# ir_remote_v3.net
KiCad netlist of a schematic drawn in EAGLE
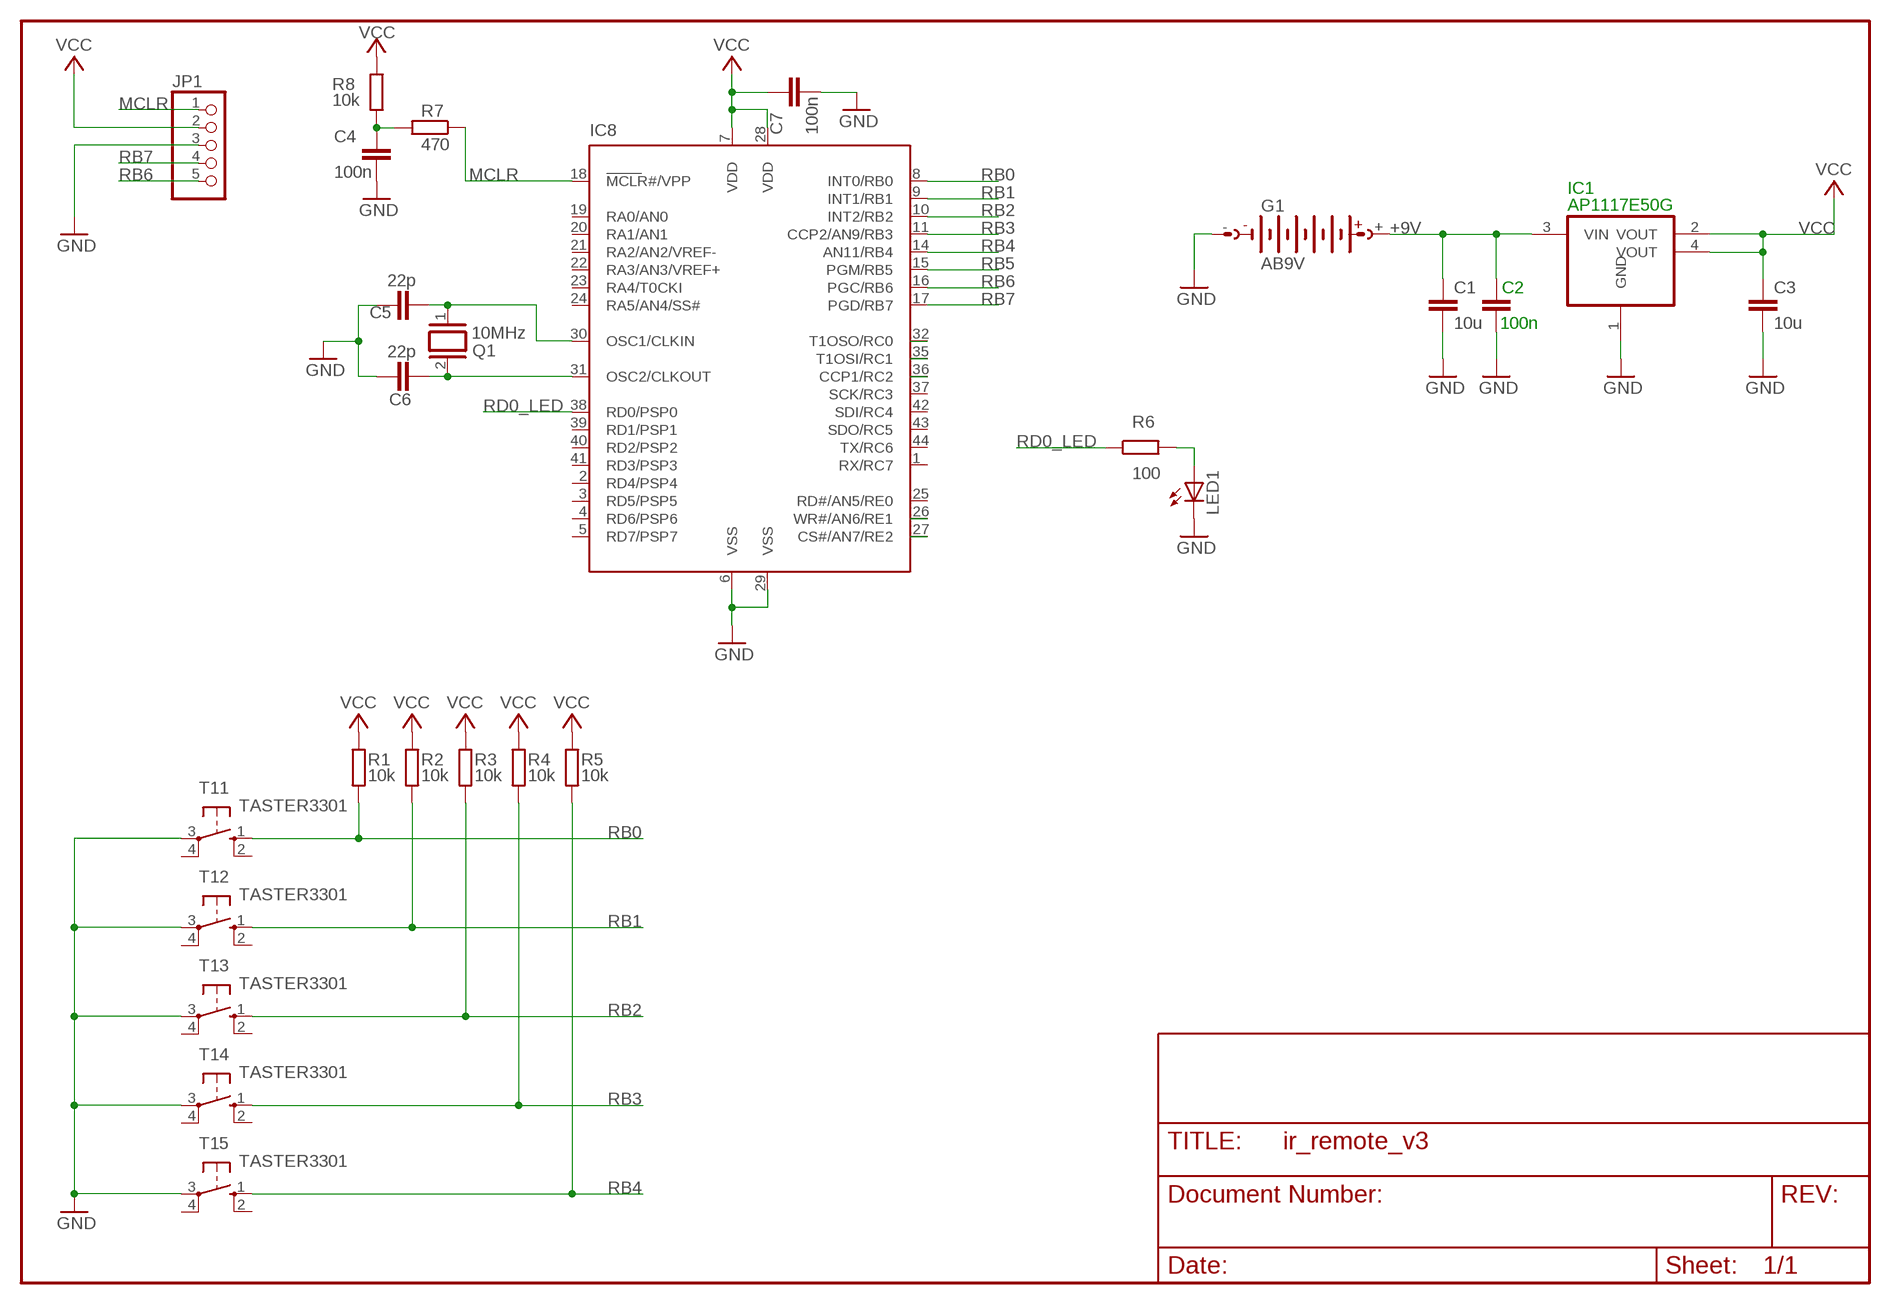
[diagram p0: schematic, sheet 1]

(export (version "E")
  (design (tool "Eeschema 10.0.6"))
  (components
    (comp (ref "C1")
      (value "10u")
      (footprint "eagle-import:C0805")
      (libsource (lib "eagle-import") (part "C-EUC0805"))
    )
    (comp (ref "C2")
      (value "100n")
      (footprint "eagle-import:C0805")
      (libsource (lib "eagle-import") (part "rcl_416_C-EUC0805"))
    )
    (comp (ref "C3")
      (value "10u")
      (footprint "eagle-import:C0805")
      (libsource (lib "eagle-import") (part "C-EUC0805"))
    )
    (comp (ref "C4")
      (value "100n")
      (footprint "eagle-import:C0805")
      (libsource (lib "eagle-import") (part "C-EUC0805"))
    )
    (comp (ref "C5")
      (value "22p")
      (footprint "eagle-import:C0603_WE")
      (libsource (lib "eagle-import") (part "C-EUC0603_WE"))
    )
    (comp (ref "C6")
      (value "22p")
      (footprint "eagle-import:C0603_WE")
      (libsource (lib "eagle-import") (part "C-EUC0603_WE"))
    )
    (comp (ref "C7")
      (value "100n")
      (footprint "eagle-import:C0805")
      (libsource (lib "eagle-import") (part "C-EUC0805"))
    )
    (comp (ref "G1")
      (value "AB9V")
      (footprint "eagle-import:AB9V")
      (libsource (lib "eagle-import") (part "AB9V"))
    )
    (comp (ref "IC1")
      (value "AP1117E50G")
      (footprint "eagle-import:SOT223")
      (libsource (lib "eagle-import") (part "REG1117-2OUT"))
    )
    (comp (ref "IC8")
      (value "PIC18F4520")
      (footprint "eagle-import:TQFP44")
      (libsource (lib "eagle-import") (part "PIC18F4520"))
    )
    (comp (ref "JP1")
      (value "PINHD-1X5")
      (footprint "eagle-import:1X05")
      (libsource (lib "eagle-import") (part "PINHD-1X5"))
    )
    (comp (ref "LED1")
      (value "LED5MM")
      (footprint "eagle-import:LED5MM")
      (libsource (lib "eagle-import") (part "LED5MM"))
    )
    (comp (ref "Q1")
      (value "10MHz")
      (footprint "eagle-import:QUARZ_HC5032_2")
      (libsource (lib "eagle-import") (part "XTAL_HC5032"))
    )
    (comp (ref "R1")
      (value "10k")
      (footprint "eagle-import:M0805")
      (libsource (lib "eagle-import") (part "R-EU_M0805"))
    )
    (comp (ref "R2")
      (value "10k")
      (footprint "eagle-import:M0805")
      (libsource (lib "eagle-import") (part "R-EU_M0805"))
    )
    (comp (ref "R3")
      (value "10k")
      (footprint "eagle-import:M0805")
      (libsource (lib "eagle-import") (part "R-EU_M0805"))
    )
    (comp (ref "R4")
      (value "10k")
      (footprint "eagle-import:M0805")
      (libsource (lib "eagle-import") (part "R-EU_M0805"))
    )
    (comp (ref "R5")
      (value "10k")
      (footprint "eagle-import:M0805")
      (libsource (lib "eagle-import") (part "R-EU_M0805"))
    )
    (comp (ref "R6")
      (value "100")
      (footprint "eagle-import:M0805")
      (libsource (lib "eagle-import") (part "R-EU_M0805"))
    )
    (comp (ref "R7")
      (value "470")
      (footprint "eagle-import:M0805")
      (libsource (lib "eagle-import") (part "R-EU_M0805"))
    )
    (comp (ref "R8")
      (value "10k")
      (footprint "eagle-import:M0805")
      (libsource (lib "eagle-import") (part "R-EU_M0805"))
    )
    (comp (ref "T11")
      (value "TASTER3301")
      (footprint "eagle-import:TASTER3301")
      (libsource (lib "eagle-import") (part "TASTER3301"))
    )
    (comp (ref "T12")
      (value "TASTER3301")
      (footprint "eagle-import:TASTER3301")
      (libsource (lib "eagle-import") (part "TASTER3301"))
    )
    (comp (ref "T13")
      (value "TASTER3301")
      (footprint "eagle-import:TASTER3301")
      (libsource (lib "eagle-import") (part "TASTER3301"))
    )
    (comp (ref "T14")
      (value "TASTER3301")
      (footprint "eagle-import:TASTER3301")
      (libsource (lib "eagle-import") (part "TASTER3301"))
    )
    (comp (ref "T15")
      (value "TASTER3301")
      (footprint "eagle-import:TASTER3301")
      (libsource (lib "eagle-import") (part "TASTER3301"))
    )
  )
  (nets
    (net (code "1") (name "/+9V") (class "Default")
      (node (ref "C1") (pin "1") (pinfunction "1_1") (pintype "passive"))
      (node (ref "C2") (pin "1") (pinfunction "1_1") (pintype "passive"))
      (node (ref "G1") (pin "+") (pinfunction "+_+") (pintype "passive"))
      (node (ref "IC1") (pin "3") (pinfunction "VIN_3") (pintype "input"))
    )
    (net (code "2") (name "/MCLR") (class "Default")
      (node (ref "IC8") (pin "18") (pinfunction "MCLR#/VPP_18") (pintype "input"))
      (node (ref "JP1") (pin "1") (pinfunction "1_1") (pintype "passive"))
      (node (ref "R7") (pin "1") (pinfunction "1_1") (pintype "passive"))
    )
    (net (code "3") (name "/RB0") (class "Default")
      (node (ref "IC8") (pin "8") (pinfunction "INT0/RB0_8") (pintype "bidirectional"))
      (node (ref "R1") (pin "2") (pinfunction "2_2") (pintype "passive"))
      (node (ref "T11") (pin "1") (pinfunction "S_1") (pintype "passive"))
    )
    (net (code "4") (name "/RB1") (class "Default")
      (node (ref "IC8") (pin "35") (pinfunction "T1OSI/RC1_35") (pintype "bidirectional"))
      (node (ref "IC8") (pin "9") (pinfunction "INT1/RB1_9") (pintype "bidirectional"))
      (node (ref "R2") (pin "2") (pinfunction "2_2") (pintype "passive"))
      (node (ref "T12") (pin "1") (pinfunction "S_1") (pintype "passive"))
    )
    (net (code "5") (name "/RB2") (class "Default")
      (node (ref "IC8") (pin "10") (pinfunction "INT2/RB2_10") (pintype "bidirectional"))
      (node (ref "IC8") (pin "32") (pinfunction "T1OSO/RC0_32") (pintype "bidirectional"))
      (node (ref "R3") (pin "2") (pinfunction "2_2") (pintype "passive"))
      (node (ref "T13") (pin "1") (pinfunction "S_1") (pintype "passive"))
    )
    (net (code "6") (name "/RB3") (class "Default")
      (node (ref "IC8") (pin "11") (pinfunction "CCP2/AN9/RB3_11") (pintype "bidirectional"))
      (node (ref "R4") (pin "2") (pinfunction "2_2") (pintype "passive"))
      (node (ref "T14") (pin "1") (pinfunction "S_1") (pintype "passive"))
    )
    (net (code "7") (name "/RB4") (class "Default")
      (node (ref "IC8") (pin "14") (pinfunction "AN11/RB4_14") (pintype "bidirectional"))
      (node (ref "R5") (pin "2") (pinfunction "2_2") (pintype "passive"))
      (node (ref "T15") (pin "1") (pinfunction "S_1") (pintype "passive"))
    )
    (net (code "8") (name "/RB5") (class "Default")
      (node (ref "IC8") (pin "15") (pinfunction "PGM/RB5_15") (pintype "bidirectional"))
    )
    (net (code "9") (name "/RB6") (class "Default")
      (node (ref "IC8") (pin "16") (pinfunction "PGC/RB6_16") (pintype "bidirectional"))
      (node (ref "JP1") (pin "5") (pinfunction "5_5") (pintype "passive"))
    )
    (net (code "10") (name "/RB7") (class "Default")
      (node (ref "IC8") (pin "17") (pinfunction "PGD/RB7_17") (pintype "bidirectional"))
      (node (ref "JP1") (pin "4") (pinfunction "4_4") (pintype "passive"))
    )
    (net (code "11") (name "/RD0_LED") (class "Default")
      (node (ref "IC8") (pin "38") (pinfunction "RD0/PSP0_38") (pintype "bidirectional"))
      (node (ref "R6") (pin "1") (pinfunction "1_1") (pintype "passive"))
    )
    (net (code "12") (name "GND") (class "Default")
      (node (ref "C1") (pin "2") (pinfunction "2_2") (pintype "passive"))
      (node (ref "C2") (pin "2") (pinfunction "2_2") (pintype "passive"))
      (node (ref "C3") (pin "2") (pinfunction "2_2") (pintype "passive"))
      (node (ref "C4") (pin "2") (pinfunction "2_2") (pintype "passive"))
      (node (ref "C5") (pin "1") (pinfunction "1_1") (pintype "passive"))
      (node (ref "C6") (pin "1") (pinfunction "1_1") (pintype "passive"))
      (node (ref "C7") (pin "2") (pinfunction "2_2") (pintype "passive"))
      (node (ref "G1") (pin "-") (pinfunction "-_-") (pintype "passive"))
      (node (ref "IC1") (pin "1") (pinfunction "GND_1") (pintype "power_in"))
      (node (ref "IC8") (pin "29") (pinfunction "VSS_29") (pintype "bidirectional"))
      (node (ref "IC8") (pin "6") (pinfunction "VSS_6") (pintype "bidirectional"))
      (node (ref "JP1") (pin "3") (pinfunction "3_3") (pintype "passive"))
      (node (ref "LED1") (pin "K") (pinfunction "C_K") (pintype "passive"))
      (node (ref "T11") (pin "3") (pinfunction "P_3") (pintype "passive"))
      (node (ref "T12") (pin "3") (pinfunction "P_3") (pintype "passive"))
      (node (ref "T13") (pin "3") (pinfunction "P_3") (pintype "passive"))
      (node (ref "T14") (pin "3") (pinfunction "P_3") (pintype "passive"))
      (node (ref "T15") (pin "3") (pinfunction "P_3") (pintype "passive"))
    )
    (net (code "13") (name "Net-(C4-Pad1)") (class "Default")
      (node (ref "C4") (pin "1") (pinfunction "1_1") (pintype "passive"))
      (node (ref "R7") (pin "2") (pinfunction "2_2") (pintype "passive"))
      (node (ref "R8") (pin "2") (pinfunction "2_2") (pintype "passive"))
    )
    (net (code "14") (name "Net-(IC8-OSC1{slash}CLKIN)") (class "Default")
      (node (ref "C5") (pin "2") (pinfunction "2_2") (pintype "passive"))
      (node (ref "IC8") (pin "30") (pinfunction "OSC1/CLKIN_30") (pintype "input"))
      (node (ref "Q1") (pin "1") (pinfunction "1_1") (pintype "passive"))
    )
    (net (code "15") (name "Net-(IC8-OSC2{slash}CLKOUT)") (class "Default")
      (node (ref "C6") (pin "2") (pinfunction "2_2") (pintype "passive"))
      (node (ref "IC8") (pin "31") (pinfunction "OSC2/CLKOUT_31") (pintype "output"))
      (node (ref "Q1") (pin "2") (pinfunction "2_2") (pintype "passive"))
    )
    (net (code "16") (name "Net-(LED1-PadA)") (class "Default")
      (node (ref "LED1") (pin "A") (pinfunction "A_A") (pintype "passive"))
      (node (ref "R6") (pin "2") (pinfunction "2_2") (pintype "passive"))
    )
    (net (code "17") (name "VCC") (class "Default")
      (node (ref "C3") (pin "1") (pinfunction "1_1") (pintype "passive"))
      (node (ref "C7") (pin "1") (pinfunction "1_1") (pintype "passive"))
      (node (ref "IC1") (pin "2") (pinfunction "VOUT_2") (pintype "output"))
      (node (ref "IC1") (pin "4") (pinfunction "VOUT_4") (pintype "bidirectional"))
      (node (ref "IC8") (pin "28") (pinfunction "VDD_28") (pintype "bidirectional"))
      (node (ref "IC8") (pin "7") (pinfunction "VDD_7") (pintype "bidirectional"))
      (node (ref "JP1") (pin "2") (pinfunction "2_2") (pintype "passive"))
      (node (ref "R1") (pin "1") (pinfunction "1_1") (pintype "passive"))
      (node (ref "R2") (pin "1") (pinfunction "1_1") (pintype "passive"))
      (node (ref "R3") (pin "1") (pinfunction "1_1") (pintype "passive"))
      (node (ref "R4") (pin "1") (pinfunction "1_1") (pintype "passive"))
      (node (ref "R5") (pin "1") (pinfunction "1_1") (pintype "passive"))
      (node (ref "R8") (pin "1") (pinfunction "1_1") (pintype "passive"))
    )
    (net (code "18") (name "unconnected-(IC8-CCP1{slash}RC2-Pad36)") (class "Default")
      (node (ref "IC8") (pin "36") (pinfunction "CCP1/RC2_36") (pintype "bidirectional"))
    )
    (net (code "19") (name "unconnected-(IC8-CS#{slash}AN7{slash}RE2-Pad27)") (class "Default")
      (node (ref "IC8") (pin "27") (pinfunction "CS#/AN7/RE2_27") (pintype "bidirectional"))
    )
    (net (code "20") (name "unconnected-(IC8-RA0{slash}AN0-Pad19)") (class "Default")
      (node (ref "IC8") (pin "19") (pinfunction "RA0/AN0_19") (pintype "bidirectional"))
    )
    (net (code "21") (name "unconnected-(IC8-RA1{slash}AN1-Pad20)") (class "Default")
      (node (ref "IC8") (pin "20") (pinfunction "RA1/AN1_20") (pintype "bidirectional"))
    )
    (net (code "22") (name "unconnected-(IC8-RA2{slash}AN2{slash}VREF--Pad21)") (class "Default")
      (node (ref "IC8") (pin "21") (pinfunction "RA2/AN2/VREF-_21") (pintype "bidirectional"))
    )
    (net (code "23") (name "unconnected-(IC8-RA3{slash}AN3{slash}VREF+-Pad22)") (class "Default")
      (node (ref "IC8") (pin "22") (pinfunction "RA3/AN3/VREF+_22") (pintype "bidirectional"))
    )
    (net (code "24") (name "unconnected-(IC8-RA4{slash}T0CKI-Pad23)") (class "Default")
      (node (ref "IC8") (pin "23") (pinfunction "RA4/T0CKI_23") (pintype "bidirectional"))
    )
    (net (code "25") (name "unconnected-(IC8-RA5{slash}AN4{slash}SS#-Pad24)") (class "Default")
      (node (ref "IC8") (pin "24") (pinfunction "RA5/AN4/SS#_24") (pintype "bidirectional"))
    )
    (net (code "26") (name "unconnected-(IC8-RD#{slash}AN5{slash}RE0-Pad25)") (class "Default")
      (node (ref "IC8") (pin "25") (pinfunction "RD#/AN5/RE0_25") (pintype "bidirectional"))
    )
    (net (code "27") (name "unconnected-(IC8-RD1{slash}PSP1-Pad39)") (class "Default")
      (node (ref "IC8") (pin "39") (pinfunction "RD1/PSP1_39") (pintype "bidirectional"))
    )
    (net (code "28") (name "unconnected-(IC8-RD2{slash}PSP2-Pad40)") (class "Default")
      (node (ref "IC8") (pin "40") (pinfunction "RD2/PSP2_40") (pintype "bidirectional"))
    )
    (net (code "29") (name "unconnected-(IC8-RD3{slash}PSP3-Pad41)") (class "Default")
      (node (ref "IC8") (pin "41") (pinfunction "RD3/PSP3_41") (pintype "bidirectional"))
    )
    (net (code "30") (name "unconnected-(IC8-RD4{slash}PSP4-Pad2)") (class "Default")
      (node (ref "IC8") (pin "2") (pinfunction "RD4/PSP4_2") (pintype "bidirectional"))
    )
    (net (code "31") (name "unconnected-(IC8-RD5{slash}PSP5-Pad3)") (class "Default")
      (node (ref "IC8") (pin "3") (pinfunction "RD5/PSP5_3") (pintype "bidirectional"))
    )
    (net (code "32") (name "unconnected-(IC8-RD6{slash}PSP6-Pad4)") (class "Default")
      (node (ref "IC8") (pin "4") (pinfunction "RD6/PSP6_4") (pintype "bidirectional"))
    )
    (net (code "33") (name "unconnected-(IC8-RD7{slash}PSP7-Pad5)") (class "Default")
      (node (ref "IC8") (pin "5") (pinfunction "RD7/PSP7_5") (pintype "bidirectional"))
    )
    (net (code "34") (name "unconnected-(IC8-RX{slash}RC7-Pad1)") (class "Default")
      (node (ref "IC8") (pin "1") (pinfunction "RX/RC7_1") (pintype "bidirectional"))
    )
    (net (code "35") (name "unconnected-(IC8-SCK{slash}RC3-Pad37)") (class "Default")
      (node (ref "IC8") (pin "37") (pinfunction "SCK/RC3_37") (pintype "bidirectional"))
    )
    (net (code "36") (name "unconnected-(IC8-SDI{slash}RC4-Pad42)") (class "Default")
      (node (ref "IC8") (pin "42") (pinfunction "SDI/RC4_42") (pintype "bidirectional"))
    )
    (net (code "37") (name "unconnected-(IC8-SDO{slash}RC5-Pad43)") (class "Default")
      (node (ref "IC8") (pin "43") (pinfunction "SDO/RC5_43") (pintype "bidirectional"))
    )
    (net (code "38") (name "unconnected-(IC8-TX{slash}RC6-Pad44)") (class "Default")
      (node (ref "IC8") (pin "44") (pinfunction "TX/RC6_44") (pintype "bidirectional"))
    )
    (net (code "39") (name "unconnected-(IC8-WR#{slash}AN6{slash}RE1-Pad26)") (class "Default")
      (node (ref "IC8") (pin "26") (pinfunction "WR#/AN6/RE1_26") (pintype "bidirectional"))
    )
    (net (code "40") (name "unconnected-(T11-P1-Pad4)") (class "Default")
      (node (ref "T11") (pin "4") (pinfunction "P1_4") (pintype "passive"))
    )
    (net (code "41") (name "unconnected-(T11-S1-Pad2)") (class "Default")
      (node (ref "T11") (pin "2") (pinfunction "S1_2") (pintype "passive"))
    )
    (net (code "42") (name "unconnected-(T12-P1-Pad4)") (class "Default")
      (node (ref "T12") (pin "4") (pinfunction "P1_4") (pintype "passive"))
    )
    (net (code "43") (name "unconnected-(T12-S1-Pad2)") (class "Default")
      (node (ref "T12") (pin "2") (pinfunction "S1_2") (pintype "passive"))
    )
    (net (code "44") (name "unconnected-(T13-P1-Pad4)") (class "Default")
      (node (ref "T13") (pin "4") (pinfunction "P1_4") (pintype "passive"))
    )
    (net (code "45") (name "unconnected-(T13-S1-Pad2)") (class "Default")
      (node (ref "T13") (pin "2") (pinfunction "S1_2") (pintype "passive"))
    )
    (net (code "46") (name "unconnected-(T14-P1-Pad4)") (class "Default")
      (node (ref "T14") (pin "4") (pinfunction "P1_4") (pintype "passive"))
    )
    (net (code "47") (name "unconnected-(T14-S1-Pad2)") (class "Default")
      (node (ref "T14") (pin "2") (pinfunction "S1_2") (pintype "passive"))
    )
    (net (code "48") (name "unconnected-(T15-P1-Pad4)") (class "Default")
      (node (ref "T15") (pin "4") (pinfunction "P1_4") (pintype "passive"))
    )
    (net (code "49") (name "unconnected-(T15-S1-Pad2)") (class "Default")
      (node (ref "T15") (pin "2") (pinfunction "S1_2") (pintype "passive"))
    )
  )
)
